# MOSFETS.net
KiCad netlist of a schematic drawn in Altium Designer
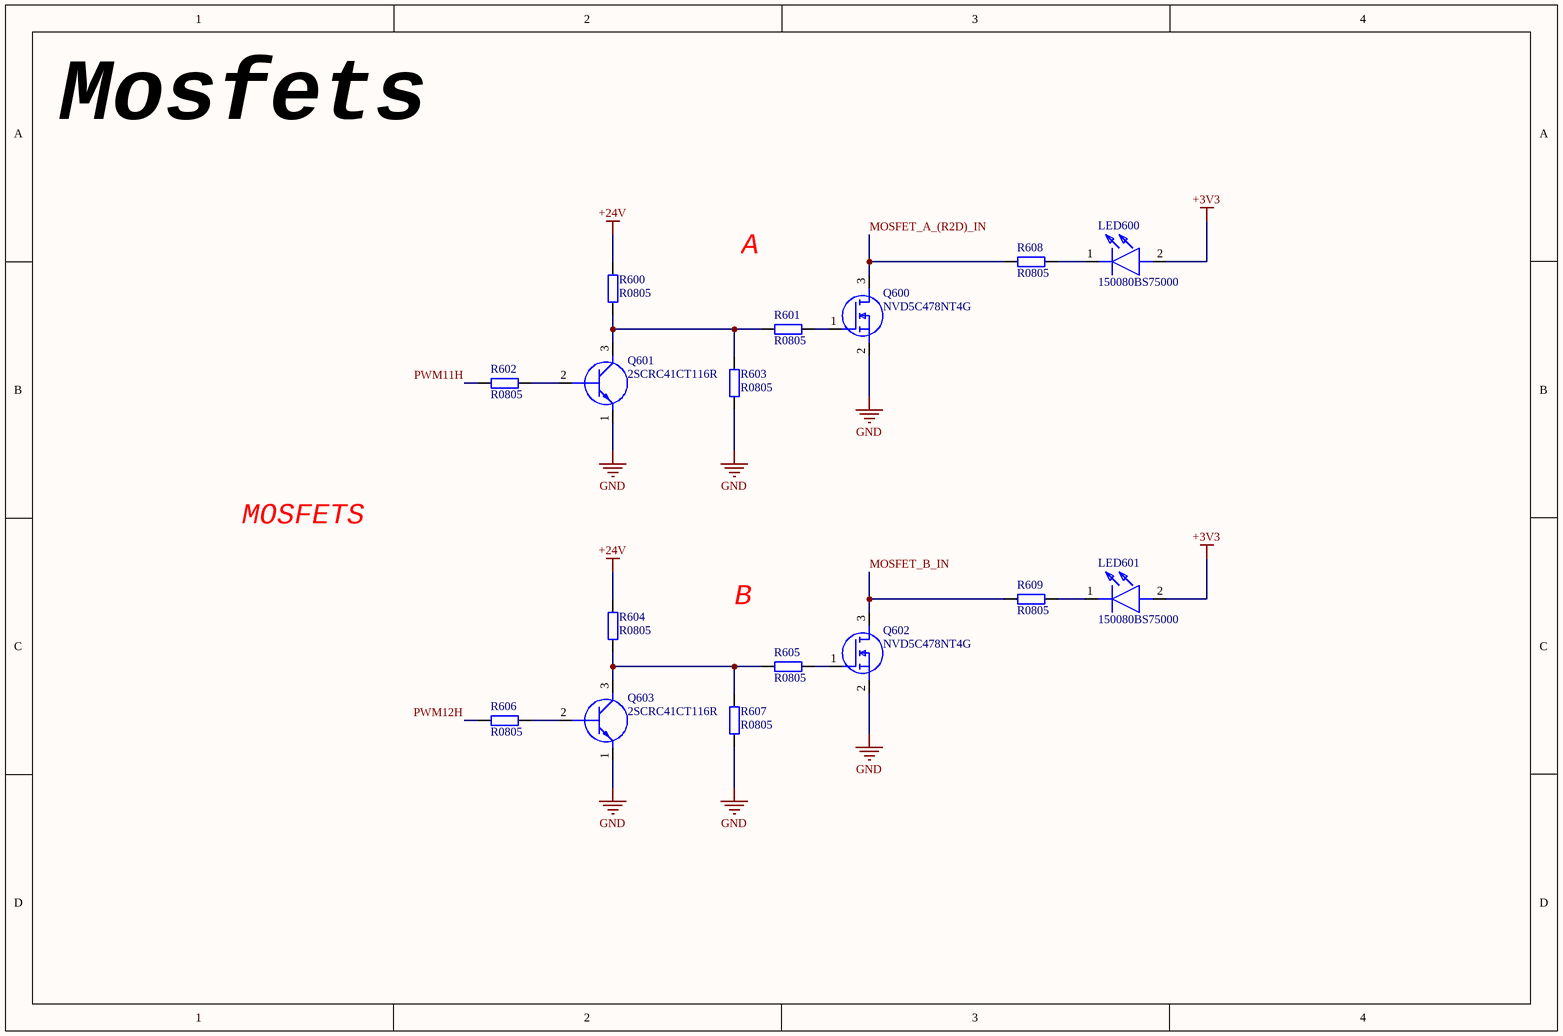
[diagram p0: MOSFETS.SchDoc]

(export (version "E")
  (design (tool "Eeschema 10.0.6"))
  (components
    (comp (ref "LED600")
      (value "150080BS75000")
      (footprint "LEDC2012X80N")
      (description "LED")
      (fields (field (name "MOUSER PART NUMBER") "710-150080BS75000"))
      (libsource (lib "Pedro_Integrated_Library") (part "150080BS75000"))
    )
    (comp (ref "LED601")
      (value "150080BS75000")
      (footprint "LEDC2012X80N")
      (description "LED")
      (fields (field (name "MOUSER PART NUMBER") "710-150080BS75000"))
      (libsource (lib "Pedro_Integrated_Library") (part "150080BS75000"))
    )
    (comp (ref "Q600")
      (value "NVD5C478NT4G")
      (footprint "DPAK_(SINGLE-GAUGE)_TO-252(369C)_ISSUE_F")
      (description "MOSFET (N-Channel)")
      (fields (field (name "MOUSER PART NUMBER") "863-NVD5C478NT4G"))
      (libsource (lib "Pedro_Integrated_Library") (part "NVD5C478NT4G"))
    )
    (comp (ref "Q601")
      (value "2SCRC41CT116R")
      (footprint "Pedro_pcb_lib:SST2222AT116")
      (description "Transistor BJT NPN")
      (fields (field (name "MOUSER PART NUMBER") "755-2SCRC41CT116"))
      (libsource (lib "*") (part "2SCRC41CT116R"))
    )
    (comp (ref "Q602")
      (value "NVD5C478NT4G")
      (footprint "DPAK_(SINGLE-GAUGE)_TO-252(369C)_ISSUE_F")
      (description "MOSFET (N-Channel)")
      (fields (field (name "MOUSER PART NUMBER") "863-NVD5C478NT4G"))
      (libsource (lib "Pedro_Integrated_Library") (part "NVD5C478NT4G"))
    )
    (comp (ref "Q603")
      (value "2SCRC41CT116R")
      (footprint "Pedro_pcb_lib:SST2222AT116")
      (description "Transistor BJT NPN")
      (fields (field (name "MOUSER PART NUMBER") "755-2SCRC41CT116"))
      (libsource (lib "*") (part "2SCRC41CT116R"))
    )
    (comp (ref "R600")
      (value "R0805")
      (footprint "RES_0805")
      (description "Resistor SMD 0805")
      (libsource (lib "Schematic-Lib-PhilsLab") (part "RES_0805"))
    )
    (comp (ref "R601")
      (value "R0805")
      (footprint "RES_0805")
      (description "Resistor SMD 0805")
      (libsource (lib "Schematic-Lib-PhilsLab") (part "RES_0805"))
    )
    (comp (ref "R602")
      (value "R0805")
      (footprint "RES_0805")
      (description "Resistor SMD 0805")
      (libsource (lib "Schematic-Lib-PhilsLab") (part "RES_0805"))
    )
    (comp (ref "R603")
      (value "R0805")
      (footprint "RES_0805")
      (description "Resistor SMD 0805")
      (libsource (lib "Schematic-Lib-PhilsLab") (part "RES_0805"))
    )
    (comp (ref "R604")
      (value "R0805")
      (footprint "RES_0805")
      (description "Resistor SMD 0805")
      (libsource (lib "Schematic-Lib-PhilsLab") (part "RES_0805"))
    )
    (comp (ref "R605")
      (value "R0805")
      (footprint "RES_0805")
      (description "Resistor SMD 0805")
      (libsource (lib "Schematic-Lib-PhilsLab") (part "RES_0805"))
    )
    (comp (ref "R606")
      (value "R0805")
      (footprint "RES_0805")
      (description "Resistor SMD 0805")
      (libsource (lib "Schematic-Lib-PhilsLab") (part "RES_0805"))
    )
    (comp (ref "R607")
      (value "R0805")
      (footprint "RES_0805")
      (description "Resistor SMD 0805")
      (libsource (lib "Schematic-Lib-PhilsLab") (part "RES_0805"))
    )
    (comp (ref "R608")
      (value "R0805")
      (footprint "RES_0805")
      (description "Resistor SMD 0805")
      (libsource (lib "Schematic-Lib-PhilsLab") (part "RES_0805"))
    )
    (comp (ref "R609")
      (value "R0805")
      (footprint "RES_0805")
      (description "Resistor SMD 0805")
      (libsource (lib "Schematic-Lib-PhilsLab") (part "RES_0805"))
    )
  )
  (nets
    (net (code "1") (name "+3V3") (class "Default")
      (node (ref "LED600") (pin "2") (pinfunction "A_2") (pintype "passive"))
      (node (ref "LED601") (pin "2") (pinfunction "A_2") (pintype "passive"))
    )
    (net (code "2") (name "+24V") (class "Default")
      (node (ref "R600") (pin "1") (pinfunction "1_1") (pintype "passive"))
      (node (ref "R604") (pin "1") (pinfunction "1_1") (pintype "passive"))
    )
    (net (code "3") (name "/MOSFET_A_(R2D)_IN") (class "Default")
      (node (ref "Q600") (pin "3") (pinfunction "D_3") (pintype "passive"))
      (node (ref "R608") (pin "1") (pinfunction "1_1") (pintype "passive"))
    )
    (net (code "4") (name "/MOSFET_B_IN") (class "Default")
      (node (ref "Q602") (pin "3") (pinfunction "D_3") (pintype "passive"))
      (node (ref "R609") (pin "1") (pinfunction "1_1") (pintype "passive"))
    )
    (net (code "5") (name "/PWM11H") (class "Default")
      (node (ref "R602") (pin "1") (pinfunction "1_1") (pintype "passive"))
    )
    (net (code "6") (name "/PWM12H") (class "Default")
      (node (ref "R606") (pin "1") (pinfunction "1_1") (pintype "passive"))
    )
    (net (code "7") (name "GND") (class "Default")
      (node (ref "Q600") (pin "2") (pinfunction "S_2") (pintype "passive"))
      (node (ref "Q601") (pin "1") (pinfunction "E_1") (pintype "passive"))
      (node (ref "Q602") (pin "2") (pinfunction "S_2") (pintype "passive"))
      (node (ref "Q603") (pin "1") (pinfunction "E_1") (pintype "passive"))
      (node (ref "R603") (pin "2") (pinfunction "2_2") (pintype "passive"))
      (node (ref "R607") (pin "2") (pinfunction "2_2") (pintype "passive"))
    )
    (net (code "8") (name "Net-(LED600-K)") (class "Default")
      (node (ref "LED600") (pin "1") (pinfunction "K_1") (pintype "passive"))
      (node (ref "R608") (pin "2") (pinfunction "2_2") (pintype "passive"))
    )
    (net (code "9") (name "Net-(LED601-K)") (class "Default")
      (node (ref "LED601") (pin "1") (pinfunction "K_1") (pintype "passive"))
      (node (ref "R609") (pin "2") (pinfunction "2_2") (pintype "passive"))
    )
    (net (code "10") (name "Net-(Q600-G)") (class "Default")
      (node (ref "Q600") (pin "1") (pinfunction "G_1") (pintype "passive"))
      (node (ref "R601") (pin "2") (pinfunction "2_2") (pintype "passive"))
    )
    (net (code "11") (name "Net-(Q601-B)") (class "Default")
      (node (ref "Q601") (pin "2") (pinfunction "B_2") (pintype "passive"))
      (node (ref "R602") (pin "2") (pinfunction "2_2") (pintype "passive"))
    )
    (net (code "12") (name "Net-(Q601-C)") (class "Default")
      (node (ref "Q601") (pin "3") (pinfunction "C_3") (pintype "passive"))
      (node (ref "R600") (pin "2") (pinfunction "2_2") (pintype "passive"))
      (node (ref "R601") (pin "1") (pinfunction "1_1") (pintype "passive"))
      (node (ref "R603") (pin "1") (pinfunction "1_1") (pintype "passive"))
    )
    (net (code "13") (name "Net-(Q602-G)") (class "Default")
      (node (ref "Q602") (pin "1") (pinfunction "G_1") (pintype "passive"))
      (node (ref "R605") (pin "2") (pinfunction "2_2") (pintype "passive"))
    )
    (net (code "14") (name "Net-(Q603-B)") (class "Default")
      (node (ref "Q603") (pin "2") (pinfunction "B_2") (pintype "passive"))
      (node (ref "R606") (pin "2") (pinfunction "2_2") (pintype "passive"))
    )
    (net (code "15") (name "Net-(Q603-C)") (class "Default")
      (node (ref "Q603") (pin "3") (pinfunction "C_3") (pintype "passive"))
      (node (ref "R604") (pin "2") (pinfunction "2_2") (pintype "passive"))
      (node (ref "R605") (pin "1") (pinfunction "1_1") (pintype "passive"))
      (node (ref "R607") (pin "1") (pinfunction "1_1") (pintype "passive"))
    )
  )
)
